# BBBL-CAN-GPS-RC-Interface.net
KiCad netlist of a schematic drawn in EAGLE
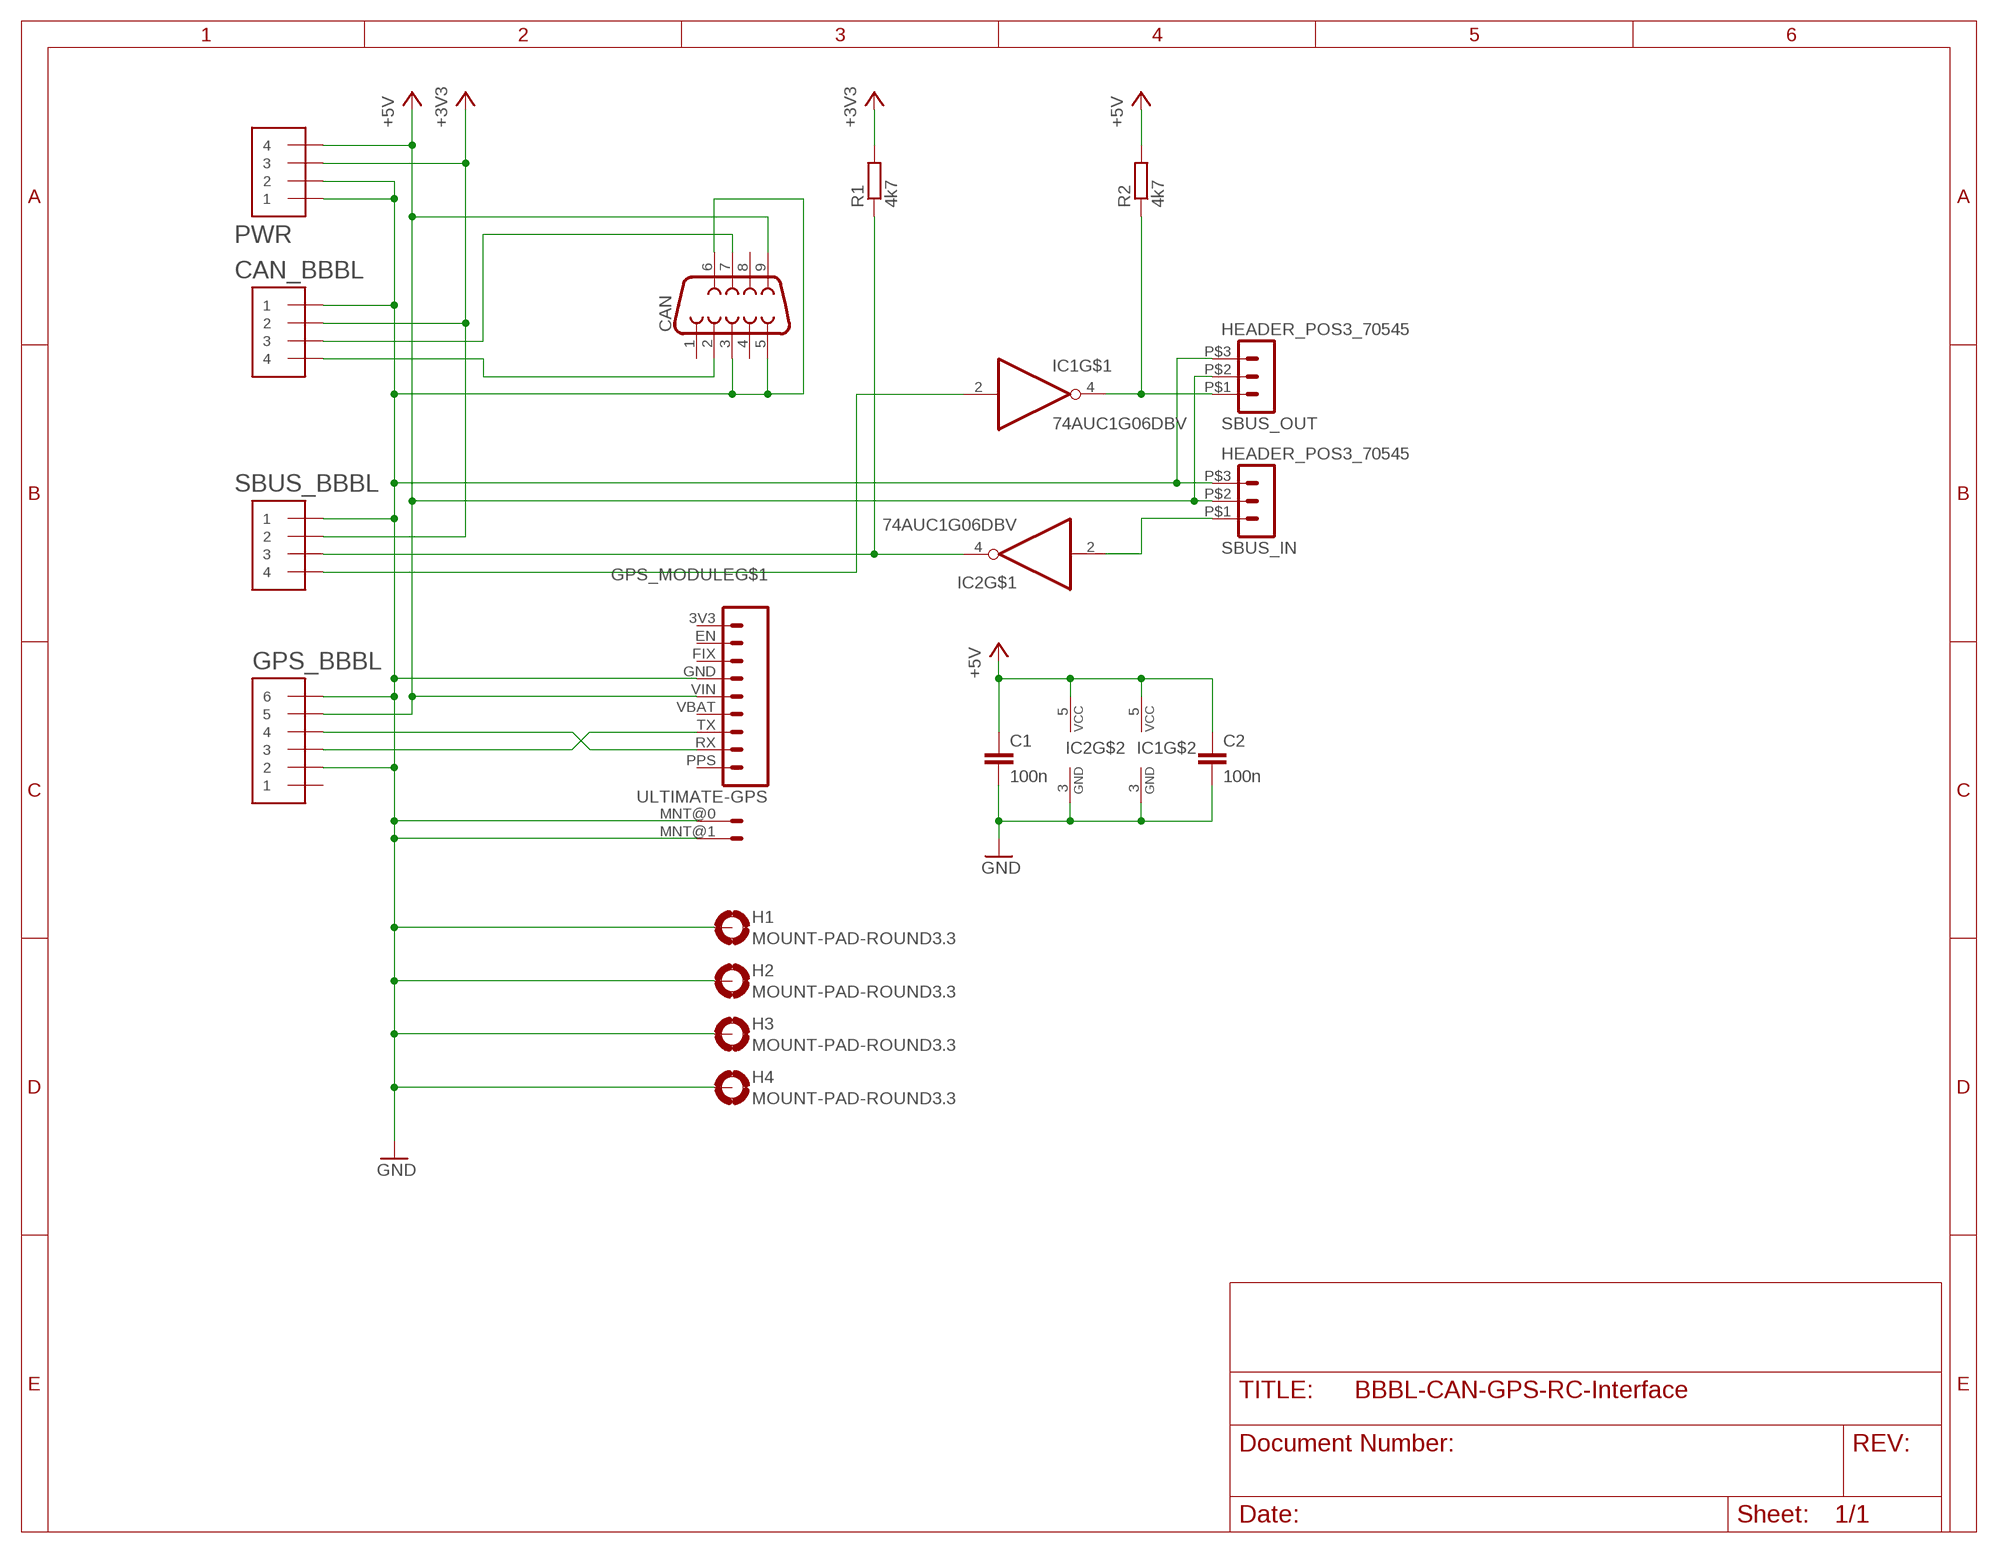
[diagram p0: schematic, sheet 1]

(export (version "E")
  (design (tool "Eeschema 10.0.6"))
  (components
    (comp (ref "C1")
      (value "100n")
      (footprint "eagle-import:C0603")
      (libsource (lib "eagle-import") (part "C-EUC0603"))
    )
    (comp (ref "C2")
      (value "100n")
      (footprint "eagle-import:C0603")
      (libsource (lib "eagle-import") (part "C-EUC0603"))
    )
    (comp (ref "CAN")
      (value "DB9MALE")
      (footprint "eagle-import:DB9_MALE")
      (libsource (lib "eagle-import") (part "DB9MALE"))
    )
    (comp (ref "CAN_BBBL")
      (value "STRAWSON_EAGLE_LIB_JST_SH_4")
      (footprint "eagle-import:STRAWSON_EAGLE_LIB_JST_SH_4_SMD")
      (libsource (lib "eagle-import") (part "STRAWSON_EAGLE_LIB_JST_SH_4"))
    )
    (comp (ref "GPS_BBBL")
      (value "STRAWSON_EAGLE_LIB_JST_SH_6")
      (footprint "eagle-import:STRAWSON_EAGLE_LIB_JST_SH_6")
      (libsource (lib "eagle-import") (part "STRAWSON_EAGLE_LIB_JST_SH_6"))
    )
    (comp (ref "GPS_MODULE")
      (value "ULTIMATE-GPS")
      (footprint "eagle-import:ULTIMATE-GPS")
      (libsource (lib "eagle-import") (part "ULTIMATE-GPS"))
    )
    (comp (ref "H1")
      (value "MOUNT-PAD-ROUND3.3")
      (footprint "eagle-import:3,3-PAD")
      (libsource (lib "eagle-import") (part "MOUNT-PAD-ROUND3.3"))
    )
    (comp (ref "H2")
      (value "MOUNT-PAD-ROUND3.3")
      (footprint "eagle-import:3,3-PAD")
      (libsource (lib "eagle-import") (part "MOUNT-PAD-ROUND3.3"))
    )
    (comp (ref "H3")
      (value "MOUNT-PAD-ROUND3.3")
      (footprint "eagle-import:3,3-PAD")
      (libsource (lib "eagle-import") (part "MOUNT-PAD-ROUND3.3"))
    )
    (comp (ref "H4")
      (value "MOUNT-PAD-ROUND3.3")
      (footprint "eagle-import:3,3-PAD")
      (libsource (lib "eagle-import") (part "MOUNT-PAD-ROUND3.3"))
    )
    (comp (ref "IC1")
      (value "74AUC1G06DBV")
      (footprint "eagle-import:SOT23-5")
      (libsource (lib "eagle-import") (part "741G06DBVAUC"))
    )
    (comp (ref "IC2")
      (value "74AUC1G06DBV")
      (footprint "eagle-import:SOT23-5")
      (libsource (lib "eagle-import") (part "741G06DBVAUC"))
    )
    (comp (ref "PWR")
      (value "STRAWSON_EAGLE_LIB_JST_SH_4")
      (footprint "eagle-import:STRAWSON_EAGLE_LIB_JST_SH_4_SMD")
      (libsource (lib "eagle-import") (part "STRAWSON_EAGLE_LIB_JST_SH_4"))
    )
    (comp (ref "R1")
      (value "4k7")
      (footprint "eagle-import:R0603")
      (libsource (lib "eagle-import") (part "R-EU_R0603"))
    )
    (comp (ref "R2")
      (value "4k7")
      (footprint "eagle-import:R0603")
      (libsource (lib "eagle-import") (part "R-EU_R0603"))
    )
    (comp (ref "SBUS_BBBL")
      (value "STRAWSON_EAGLE_LIB_JST_SH_4")
      (footprint "eagle-import:STRAWSON_EAGLE_LIB_JST_SH_4_SMD")
      (libsource (lib "eagle-import") (part "STRAWSON_EAGLE_LIB_JST_SH_4"))
    )
    (comp (ref "SBUS_IN")
      (value "HEADER_POS3_70545")
      (footprint "eagle-import:70545-POS3")
      (libsource (lib "eagle-import") (part "HEADER_POS3_?70545"))
    )
    (comp (ref "SBUS_OUT")
      (value "HEADER_POS3_70545")
      (footprint "eagle-import:70545-POS3")
      (libsource (lib "eagle-import") (part "HEADER_POS3_?70545"))
    )
  )
  (nets
    (net (code "1") (name "+3V3") (class "Default")
      (node (ref "CAN_BBBL") (pin "2") (pinfunction "2_2") (pintype "bidirectional"))
      (node (ref "PWR") (pin "3") (pinfunction "3_3") (pintype "bidirectional"))
      (node (ref "R1") (pin "2") (pinfunction "2_2") (pintype "passive"))
      (node (ref "SBUS_BBBL") (pin "2") (pinfunction "2_2") (pintype "bidirectional"))
    )
    (net (code "2") (name "+5V") (class "Default")
      (node (ref "C1") (pin "1") (pinfunction "1_1") (pintype "passive"))
      (node (ref "C2") (pin "1") (pinfunction "1_1") (pintype "passive"))
      (node (ref "CAN") (pin "9") (pinfunction "9_9") (pintype "passive"))
      (node (ref "GPS_BBBL") (pin "5") (pinfunction "5_5") (pintype "bidirectional"))
      (node (ref "GPS_MODULE") (pin "VIN") (pinfunction "5_VIN") (pintype "passive"))
      (node (ref "IC1") (pin "5") (pinfunction "VCC_5") (pintype "power_in"))
      (node (ref "IC2") (pin "5") (pinfunction "VCC_5") (pintype "power_in"))
      (node (ref "PWR") (pin "4") (pinfunction "4_4") (pintype "bidirectional"))
      (node (ref "R2") (pin "2") (pinfunction "2_2") (pintype "passive"))
      (node (ref "SBUS_IN") (pin "P$2") (pinfunction "2_P$2") (pintype "passive"))
      (node (ref "SBUS_OUT") (pin "P$2") (pinfunction "2_P$2") (pintype "passive"))
    )
    (net (code "3") (name "GND") (class "Default")
      (node (ref "C1") (pin "2") (pinfunction "2_2") (pintype "passive"))
      (node (ref "C2") (pin "2") (pinfunction "2_2") (pintype "passive"))
      (node (ref "CAN") (pin "3") (pinfunction "3_3") (pintype "passive"))
      (node (ref "CAN") (pin "5") (pinfunction "5_5") (pintype "passive"))
      (node (ref "CAN") (pin "6") (pinfunction "6_6") (pintype "passive"))
      (node (ref "CAN_BBBL") (pin "1") (pinfunction "1_1") (pintype "bidirectional"))
      (node (ref "GPS_BBBL") (pin "2") (pinfunction "2_2") (pintype "bidirectional"))
      (node (ref "GPS_BBBL") (pin "6") (pinfunction "6_6") (pintype "bidirectional"))
      (node (ref "GPS_MODULE") (pin "GND") (pinfunction "6_GND") (pintype "passive"))
      (node (ref "GPS_MODULE") (pin "MNT@0") (pinfunction "9_MNT@0") (pintype "passive"))
      (node (ref "GPS_MODULE") (pin "MNT@1") (pinfunction "9_MNT@1") (pintype "passive"))
      (node (ref "H1") (pin "B3,3") (pinfunction "MOUNT_B3,3") (pintype "passive"))
      (node (ref "H2") (pin "B3,3") (pinfunction "MOUNT_B3,3") (pintype "passive"))
      (node (ref "H3") (pin "B3,3") (pinfunction "MOUNT_B3,3") (pintype "passive"))
      (node (ref "H4") (pin "B3,3") (pinfunction "MOUNT_B3,3") (pintype "passive"))
      (node (ref "IC1") (pin "3") (pinfunction "GND_3") (pintype "power_in"))
      (node (ref "IC2") (pin "3") (pinfunction "GND_3") (pintype "power_in"))
      (node (ref "PWR") (pin "1") (pinfunction "1_1") (pintype "bidirectional"))
      (node (ref "PWR") (pin "2") (pinfunction "2_2") (pintype "bidirectional"))
      (node (ref "SBUS_BBBL") (pin "1") (pinfunction "1_1") (pintype "bidirectional"))
      (node (ref "SBUS_IN") (pin "P$3") (pinfunction "3_P$3") (pintype "passive"))
      (node (ref "SBUS_OUT") (pin "P$3") (pinfunction "3_P$3") (pintype "passive"))
    )
    (net (code "4") (name "Net-(CAN-Pad2)") (class "Default")
      (node (ref "CAN") (pin "2") (pinfunction "2_2") (pintype "passive"))
      (node (ref "CAN_BBBL") (pin "4") (pinfunction "4_4") (pintype "bidirectional"))
    )
    (net (code "5") (name "Net-(CAN-Pad7)") (class "Default")
      (node (ref "CAN") (pin "7") (pinfunction "7_7") (pintype "passive"))
      (node (ref "CAN_BBBL") (pin "3") (pinfunction "3_3") (pintype "bidirectional"))
    )
    (net (code "6") (name "Net-(GPS_MODULEA-2)") (class "Default")
      (node (ref "GPS_BBBL") (pin "4") (pinfunction "4_4") (pintype "bidirectional"))
      (node (ref "GPS_MODULE") (pin "RX") (pinfunction "2_RX") (pintype "passive"))
    )
    (net (code "7") (name "Net-(GPS_MODULEA-3)") (class "Default")
      (node (ref "GPS_BBBL") (pin "3") (pinfunction "3_3") (pintype "bidirectional"))
      (node (ref "GPS_MODULE") (pin "TX") (pinfunction "3_TX") (pintype "passive"))
    )
    (net (code "8") (name "Net-(IC1A-I)") (class "Default")
      (node (ref "IC1") (pin "2") (pinfunction "I_2") (pintype "input"))
      (node (ref "SBUS_BBBL") (pin "4") (pinfunction "4_4") (pintype "bidirectional"))
    )
    (net (code "9") (name "Net-(IC1A-O)") (class "Default")
      (node (ref "IC1") (pin "4") (pinfunction "O_4") (pintype "open_collector"))
      (node (ref "R2") (pin "1") (pinfunction "1_1") (pintype "passive"))
      (node (ref "SBUS_OUT") (pin "P$1") (pinfunction "1_P$1") (pintype "passive"))
    )
    (net (code "10") (name "Net-(IC2A-I)") (class "Default")
      (node (ref "IC2") (pin "2") (pinfunction "I_2") (pintype "input"))
      (node (ref "SBUS_IN") (pin "P$1") (pinfunction "1_P$1") (pintype "passive"))
    )
    (net (code "11") (name "Net-(IC2A-O)") (class "Default")
      (node (ref "IC2") (pin "4") (pinfunction "O_4") (pintype "open_collector"))
      (node (ref "R1") (pin "1") (pinfunction "1_1") (pintype "passive"))
      (node (ref "SBUS_BBBL") (pin "3") (pinfunction "3_3") (pintype "bidirectional"))
    )
    (net (code "12") (name "unconnected-(CAN-Pad1)") (class "Default")
      (node (ref "CAN") (pin "1") (pinfunction "1_1") (pintype "passive"))
    )
    (net (code "13") (name "unconnected-(CAN-Pad4)") (class "Default")
      (node (ref "CAN") (pin "4") (pinfunction "4_4") (pintype "passive"))
    )
    (net (code "14") (name "unconnected-(CAN-Pad8)") (class "Default")
      (node (ref "CAN") (pin "8") (pinfunction "8_8") (pintype "passive"))
    )
    (net (code "15") (name "unconnected-(GPS_BBBL-Pad1)") (class "Default")
      (node (ref "GPS_BBBL") (pin "1") (pinfunction "1_1") (pintype "bidirectional"))
    )
    (net (code "16") (name "unconnected-(GPS_MODULEA-1-PadPPS)") (class "Default")
      (node (ref "GPS_MODULE") (pin "PPS") (pinfunction "1_PPS") (pintype "passive"))
    )
    (net (code "17") (name "unconnected-(GPS_MODULEA-4-PadVBAT)") (class "Default")
      (node (ref "GPS_MODULE") (pin "VBAT") (pinfunction "4_VBAT") (pintype "passive"))
    )
    (net (code "18") (name "unconnected-(GPS_MODULEA-7-PadFIX)") (class "Default")
      (node (ref "GPS_MODULE") (pin "FIX") (pinfunction "7_FIX") (pintype "passive"))
    )
    (net (code "19") (name "unconnected-(GPS_MODULEA-8-PadEN)") (class "Default")
      (node (ref "GPS_MODULE") (pin "EN") (pinfunction "8_EN") (pintype "passive"))
    )
    (net (code "20") (name "unconnected-(GPS_MODULEA-9-Pad3V3)") (class "Default")
      (node (ref "GPS_MODULE") (pin "3V3") (pinfunction "9_3V3") (pintype "passive"))
    )
  )
)
